# Power.net
KiCad netlist of a schematic drawn in Altium Designer
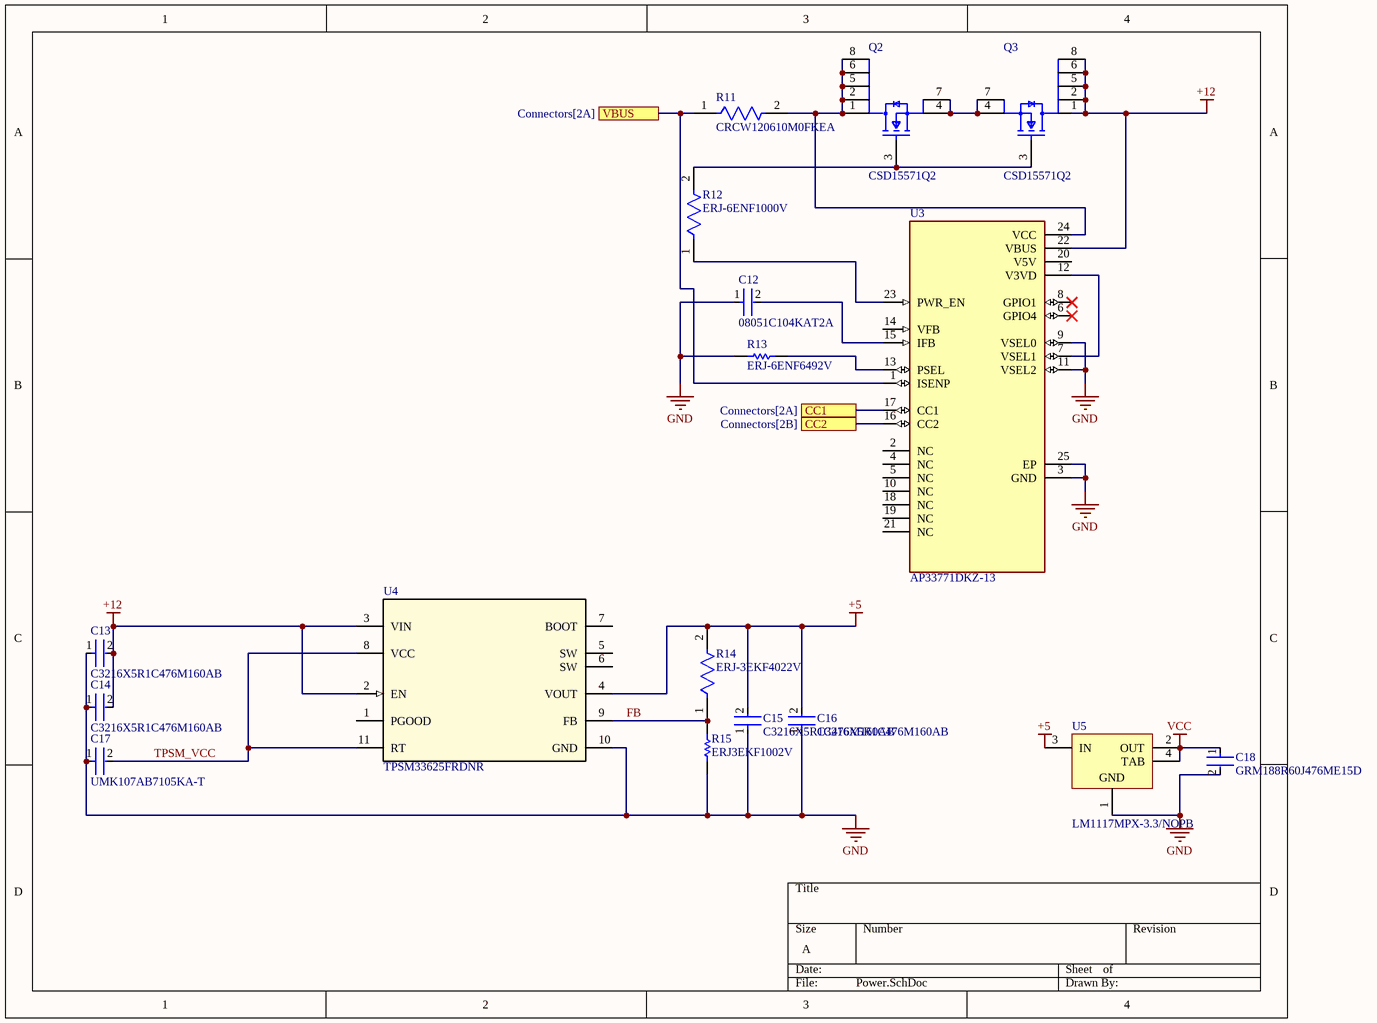
[diagram p0: Power.SchDoc]

(export (version "E")
  (design (tool "Eeschema 10.0.6"))
  (components
    (comp (ref "C12")
      (value "08051C104KAT2A")
      (footprint "FP-0805-L_2_01_0_2-W_1_25-IPC_B")
      (description "General Purpose Ceramic Capacitor, 0805, 100nF, 10%, X7R, 15%, 100V")
      (fields (field (name "VOLTAGE") "100V") (field (name "TOLERANCE") "10%"))
      (libsource (lib "Altium Content Vault") (part "b4654b650e69147ec39a6b967a45e02"))
    )
    (comp (ref "C13")
      (value "C3216X5R1C476M160AB")
      (footprint "FP-C3216-160-0_2-MFG")
      (description "Multilayer Ceramic Capacitors 47uF ±20% 16V X5R SMD 1206")
      (fields (field (name "TOLERANCE") "20%"))
      (libsource (lib "Altium Content Vault") (part "11868f565c42a9108669ba33697ecf6"))
    )
    (comp (ref "C14")
      (value "C3216X5R1C476M160AB")
      (footprint "FP-C3216-160-0_2-MFG")
      (description "Multilayer Ceramic Capacitors 47uF ±20% 16V X5R SMD 1206")
      (fields (field (name "TOLERANCE") "20%"))
      (libsource (lib "Altium Content Vault") (part "11868f565c42a9108669ba33697ecf6"))
    )
    (comp (ref "C15")
      (value "C3216X5R1C476M160AB")
      (footprint "FP-C3216-160-0_2-MFG")
      (description "Multilayer Ceramic Capacitors 47uF ±20% 16V X5R SMD 1206")
      (fields (field (name "TOLERANCE") "20%"))
      (libsource (lib "Altium Content Vault") (part "11868f565c42a9108669ba33697ecf6"))
    )
    (comp (ref "C16")
      (value "C3216X5R1C476M160AB")
      (footprint "FP-C3216-160-0_2-MFG")
      (description "Multilayer Ceramic Capacitors 47uF ±20% 16V X5R SMD 1206")
      (fields (field (name "TOLERANCE") "20%"))
      (libsource (lib "Altium Content Vault") (part "11868f565c42a9108669ba33697ecf6"))
    )
    (comp (ref "C17")
      (value "UMK107AB7105KA-T")
      (footprint "FP-0603-L_1_6_0_15-W_0_8-IPC_C")
      (description "Ceramic Capacitor General Use 1uF ±10% 50V X7R 0603")
      (fields (field (name "TOLERANCE") "10%"))
      (libsource (lib "Altium Content Vault") (part "11868f565c42a9108669ba33697ecf6"))
    )
    (comp (ref "C18")
      (value "GRM188R60J476ME15D")
      (footprint "FP-GRM188-0_2-IPC_B")
      (description "Chip Multilayer Ceramic Capacitors for General Purpose, 0603, 47uF, X5R, 15%, 20%, 6.3V")
      (fields (field (name "TOLERANCE") "20%"))
      (libsource (lib "Altium Content Vault") (part "11868f565c42a9108669ba33697ecf6"))
    )
    (comp (ref "Q2")
      (value "CSD15571Q2")
      (footprint "FP-DQK0006C-MFG")
      (description "MOSFET N-CH 20V 22A 6SON")
      (libsource (lib "Altium Content Vault") (part "311c374e0721b15468b9837d6aab788"))
    )
    (comp (ref "Q3")
      (value "CSD15571Q2")
      (footprint "FP-DQK0006C-MFG")
      (description "MOSFET N-CH 20V 22A 6SON")
      (libsource (lib "Altium Content Vault") (part "311c374e0721b15468b9837d6aab788"))
    )
    (comp (ref "R11")
      (value "CRCW120610M0FKEA")
      (footprint "FP-CRCW1206-e3-IPC_B")
      (description "RES Thick Film, 10MΩ, 1%, 0.25W, 100ppm/°C, 1206")
      (fields (field (name "TOLERANCE") "1%"))
      (libsource (lib "Altium Content Vault") (part "1029c3af85768c4190bb7ad29bc67b5"))
    )
    (comp (ref "R12")
      (value "ERJ-6ENF1000V")
      (footprint "FP-ERJ6EN-MFG")
      (description "RES SMD 100 OHM 1% 1/8W 0805")
      (fields (field (name "TOLERANCE") "1%"))
      (libsource (lib "Altium Content Vault") (part "1029c3af85768c4190bb7ad29bc67b5"))
    )
    (comp (ref "R13")
      (value "ERJ-6ENF6492V")
      (footprint "RESC2013X70X40LL20T20")
      (fields (field (name "MANUFACTURER") "Panasonic"))
      (libsource (lib "Altium Content Vault") (part "RES"))
    )
    (comp (ref "R14")
      (value "ERJ-3EKF4022V")
      (footprint "FP-ERJ3EK-IPC_C")
      (description "RES SMD 40.2K OHM 1% 1/10W 0603")
      (fields (field (name "TOLERANCE") "1%"))
      (libsource (lib "Altium Content Vault") (part "1029c3af85768c4190bb7ad29bc67b5"))
    )
    (comp (ref "R15")
      (value "ERJ3EKF1002V")
      (footprint "RESC1609X55X30LL15T15")
      (description "Chip Resistor, 10 KOhm, +/- 1%, 0.1 W, -55 to 155 degC, 0603 (1608 Metric), RoHS, Tape and Reel")
      (fields (field (name "TOLERANCE") "1%") (field (name "MANUFACTURER") "Panasonic"))
      (libsource (lib "Altium Content Vault") (part "RES-2"))
    )
    (comp (ref "U3")
      (value "AP33771DKZ-13")
      (footprint "AP33771DKZ-13:IC_AP33771DKZ-13")
      (fields (field (name "MF") "{'manufacturer': u'Diodes Incorporated'}"))
      (libsource (lib "*") (part "AP33771DKZ-13"))
    )
    (comp (ref "U4")
      (value "TPSM33625FRDNR")
      (footprint "RDN0011A-MFG")
      (description "No Description Available")
      (libsource (lib "Purdue University") (part "TPSM33625FRDNR"))
    )
    (comp (ref "U5")
      (value "LM1117MPX-3.3/NOPB")
      (footprint "DCY0004A_L")
      (description "800mA Low-Dropout Linear Regulator, 4-pin SOT-223, Pb-Free")
      (fields (field (name "MANUFACTURER") "Texas Instruments"))
      (libsource (lib "Altium Content Vault") (part "PM-REG-LM1086-SOT4"))
    )
  )
  (nets
    (net (code "1") (name "+5") (class "Default")
      (node (ref "C15") (pin "2") (pinfunction "2_2") (pintype "passive"))
      (node (ref "C16") (pin "2") (pinfunction "2_2") (pintype "passive"))
      (node (ref "R14") (pin "2") (pinfunction "2_2") (pintype "passive"))
      (node (ref "U4") (pin "4") (pinfunction "VOUT_4") (pintype "power_in"))
      (node (ref "U5") (pin "3") (pinfunction "IN_3") (pintype "power_in"))
    )
    (net (code "2") (name "+12") (class "Default")
      (node (ref "C13") (pin "2") (pinfunction "2_2") (pintype "passive"))
      (node (ref "C14") (pin "2") (pinfunction "2_2") (pintype "passive"))
      (node (ref "Q3") (pin "1") (pinfunction "D_1") (pintype "passive"))
      (node (ref "Q3") (pin "2") (pinfunction "D_2") (pintype "passive"))
      (node (ref "Q3") (pin "5") (pinfunction "D_5") (pintype "passive"))
      (node (ref "Q3") (pin "6") (pinfunction "D_6") (pintype "passive"))
      (node (ref "Q3") (pin "8") (pinfunction "D_8") (pintype "passive"))
      (node (ref "U3") (pin "22") (pinfunction "VBUS_22") (pintype "power_in"))
      (node (ref "U4") (pin "2") (pinfunction "EN_2") (pintype "input"))
      (node (ref "U4") (pin "3") (pinfunction "VIN_3") (pintype "power_in"))
    )
    (net (code "3") (name "/CC1") (class "Default")
      (node (ref "U3") (pin "17") (pinfunction "CC1_17") (pintype "bidirectional"))
    )
    (net (code "4") (name "/CC2") (class "Default")
      (node (ref "U3") (pin "16") (pinfunction "CC2_16") (pintype "bidirectional"))
    )
    (net (code "5") (name "/FB") (class "Default")
      (node (ref "R14") (pin "1") (pinfunction "1_1") (pintype "passive"))
      (node (ref "R15") (pin "2") (pinfunction "2_2") (pintype "passive"))
      (node (ref "U4") (pin "9") (pinfunction "FB_9") (pintype "passive"))
    )
    (net (code "6") (name "/TPSM_VCC") (class "Default")
      (node (ref "C17") (pin "2") (pinfunction "2_2") (pintype "passive"))
      (node (ref "U4") (pin "11") (pinfunction "RT_11") (pintype "passive"))
      (node (ref "U4") (pin "8") (pinfunction "VCC_8") (pintype "passive"))
    )
    (net (code "7") (name "/VBUS") (class "Default")
      (node (ref "R11") (pin "1") (pinfunction "1_1") (pintype "passive"))
      (node (ref "U3") (pin "1") (pinfunction "ISENP_1") (pintype "bidirectional"))
    )
    (net (code "8") (name "GND") (class "Default")
      (node (ref "C12") (pin "1") (pinfunction "1_1") (pintype "passive"))
      (node (ref "C13") (pin "1") (pinfunction "1_1") (pintype "passive"))
      (node (ref "C14") (pin "1") (pinfunction "1_1") (pintype "passive"))
      (node (ref "C15") (pin "1") (pinfunction "1_1") (pintype "passive"))
      (node (ref "C16") (pin "1") (pinfunction "1_1") (pintype "passive"))
      (node (ref "C17") (pin "1") (pinfunction "1_1") (pintype "passive"))
      (node (ref "C18") (pin "2") (pinfunction "2_2") (pintype "passive"))
      (node (ref "R13") (pin "1") (pinfunction "1_1") (pintype "passive"))
      (node (ref "R15") (pin "1") (pinfunction "1_1") (pintype "passive"))
      (node (ref "U3") (pin "11") (pinfunction "VSEL2_11") (pintype "bidirectional"))
      (node (ref "U3") (pin "25") (pinfunction "EP_25") (pintype "power_in"))
      (node (ref "U3") (pin "3") (pinfunction "GND_3") (pintype "power_in"))
      (node (ref "U3") (pin "9") (pinfunction "VSEL0_9") (pintype "bidirectional"))
      (node (ref "U4") (pin "10") (pinfunction "GND_10") (pintype "power_in"))
      (node (ref "U5") (pin "1") (pinfunction "GND_1") (pintype "power_in"))
    )
    (net (code "9") (name "Net-(Q2-G)") (class "Default")
      (node (ref "Q2") (pin "3") (pinfunction "G_3") (pintype "passive"))
      (node (ref "Q3") (pin "3") (pinfunction "G_3") (pintype "passive"))
      (node (ref "R12") (pin "2") (pinfunction "2_2") (pintype "passive"))
    )
    (net (code "10") (name "Net-(Q2-S-Pad4)") (class "Default")
      (node (ref "Q2") (pin "4") (pinfunction "S_4") (pintype "passive"))
      (node (ref "Q2") (pin "7") (pinfunction "S_7") (pintype "passive"))
      (node (ref "Q3") (pin "4") (pinfunction "S_4") (pintype "passive"))
      (node (ref "Q3") (pin "7") (pinfunction "S_7") (pintype "passive"))
    )
    (net (code "11") (name "Net-(U3-IFB)") (class "Default")
      (node (ref "C12") (pin "2") (pinfunction "2_2") (pintype "passive"))
      (node (ref "U3") (pin "15") (pinfunction "IFB_15") (pintype "input"))
    )
    (net (code "12") (name "Net-(U3-PSEL)") (class "Default")
      (node (ref "R13") (pin "2") (pinfunction "2_2") (pintype "passive"))
      (node (ref "U3") (pin "13") (pinfunction "PSEL_13") (pintype "bidirectional"))
    )
    (net (code "13") (name "Net-(U3-PWR_EN)") (class "Default")
      (node (ref "R12") (pin "1") (pinfunction "1_1") (pintype "passive"))
      (node (ref "U3") (pin "23") (pinfunction "PWR_EN_23") (pintype "input"))
    )
    (net (code "14") (name "Net-(U3-V3VD)") (class "Default")
      (node (ref "U3") (pin "12") (pinfunction "V3VD_12") (pintype "power_in"))
      (node (ref "U3") (pin "7") (pinfunction "VSEL1_7") (pintype "bidirectional"))
    )
    (net (code "15") (name "Net-(U3-VCC)") (class "Default")
      (node (ref "Q2") (pin "1") (pinfunction "D_1") (pintype "passive"))
      (node (ref "Q2") (pin "2") (pinfunction "D_2") (pintype "passive"))
      (node (ref "Q2") (pin "5") (pinfunction "D_5") (pintype "passive"))
      (node (ref "Q2") (pin "6") (pinfunction "D_6") (pintype "passive"))
      (node (ref "Q2") (pin "8") (pinfunction "D_8") (pintype "passive"))
      (node (ref "R11") (pin "2") (pinfunction "2_2") (pintype "passive"))
      (node (ref "U3") (pin "24") (pinfunction "VCC_24") (pintype "power_in"))
    )
    (net (code "16") (name "VCC") (class "Default")
      (node (ref "C18") (pin "1") (pinfunction "1_1") (pintype "passive"))
      (node (ref "U5") (pin "2") (pinfunction "OUT_2") (pintype "power_in"))
      (node (ref "U5") (pin "4") (pinfunction "TAB_4") (pintype "power_in"))
    )
    (net (code "17") (name "unconnected-(U3-GPIO1-Pad8)") (class "Default")
      (node (ref "U3") (pin "8") (pinfunction "GPIO1_8") (pintype "bidirectional+no_connect"))
    )
    (net (code "18") (name "unconnected-(U3-GPIO4-Pad6)") (class "Default")
      (node (ref "U3") (pin "6") (pinfunction "GPIO4_6") (pintype "bidirectional+no_connect"))
    )
    (net (code "19") (name "unconnected-(U3-NC-Pad2)") (class "Default")
      (node (ref "U3") (pin "2") (pinfunction "NC_2") (pintype "passive"))
    )
    (net (code "20") (name "unconnected-(U3-NC-Pad4)") (class "Default")
      (node (ref "U3") (pin "4") (pinfunction "NC_4") (pintype "passive"))
    )
    (net (code "21") (name "unconnected-(U3-NC-Pad5)") (class "Default")
      (node (ref "U3") (pin "5") (pinfunction "NC_5") (pintype "passive"))
    )
    (net (code "22") (name "unconnected-(U3-NC-Pad10)") (class "Default")
      (node (ref "U3") (pin "10") (pinfunction "NC_10") (pintype "passive"))
    )
    (net (code "23") (name "unconnected-(U3-NC-Pad18)") (class "Default")
      (node (ref "U3") (pin "18") (pinfunction "NC_18") (pintype "passive"))
    )
    (net (code "24") (name "unconnected-(U3-NC-Pad19)") (class "Default")
      (node (ref "U3") (pin "19") (pinfunction "NC_19") (pintype "passive"))
    )
    (net (code "25") (name "unconnected-(U3-NC-Pad21)") (class "Default")
      (node (ref "U3") (pin "21") (pinfunction "NC_21") (pintype "passive"))
    )
    (net (code "26") (name "unconnected-(U3-V5V-Pad20)") (class "Default")
      (node (ref "U3") (pin "20") (pinfunction "V5V_20") (pintype "power_in"))
    )
    (net (code "27") (name "unconnected-(U3-VFB-Pad14)") (class "Default")
      (node (ref "U3") (pin "14") (pinfunction "VFB_14") (pintype "input"))
    )
    (net (code "28") (name "unconnected-(U4-BOOT-Pad7)") (class "Default")
      (node (ref "U4") (pin "7") (pinfunction "BOOT_7") (pintype "passive"))
    )
    (net (code "29") (name "unconnected-(U4-PGOOD-Pad1)") (class "Default")
      (node (ref "U4") (pin "1") (pinfunction "PGOOD_1") (pintype "open_collector"))
    )
    (net (code "30") (name "unconnected-(U4-SW-Pad5)") (class "Default")
      (node (ref "U4") (pin "5") (pinfunction "SW_5") (pintype "passive"))
    )
    (net (code "31") (name "unconnected-(U4-SW-Pad6)") (class "Default")
      (node (ref "U4") (pin "6") (pinfunction "SW_6") (pintype "passive"))
    )
  )
)
